# M4QIDB-SCH-01_Sheet2.net
KiCad netlist of a schematic drawn in Altium Designer
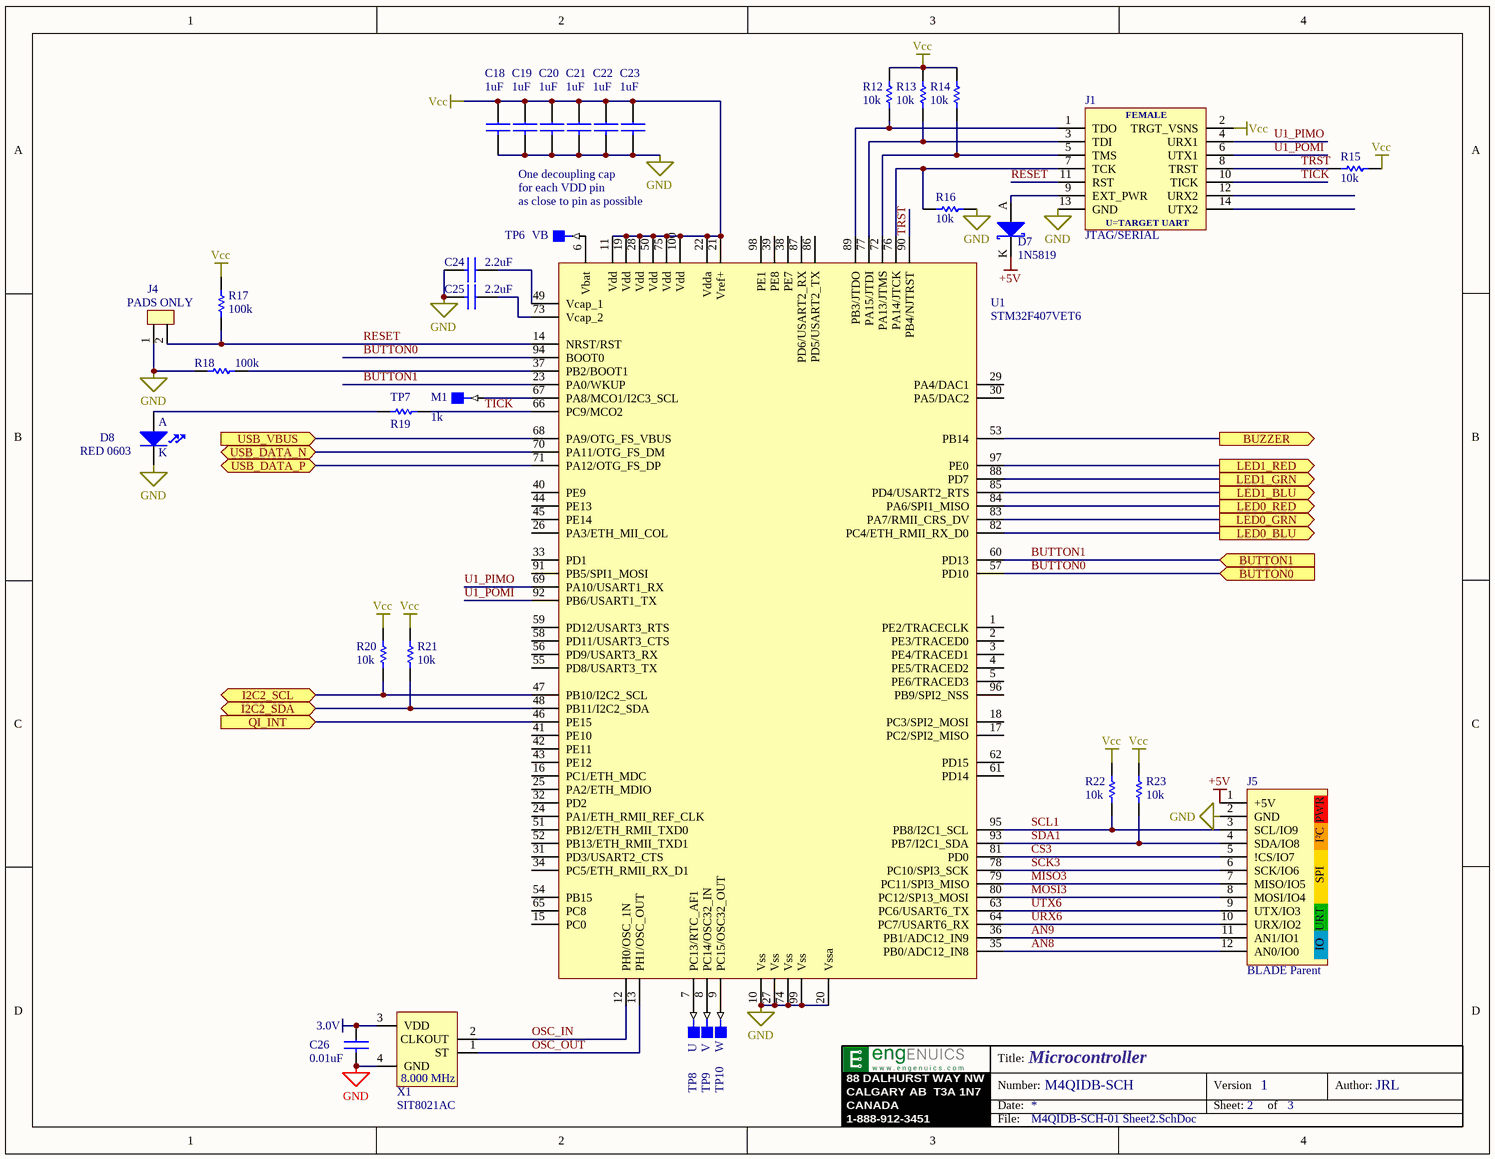
[diagram p0: M4QIDB-SCH-01 Sheet2.SchDoc]

(export (version "E")
  (design (tool "Eeschema 10.0.6"))
  (components
    (comp (ref "C18")
      (value "1uF")
      (footprint "0603 CAP3D")
      (fields
        (field (name "4. DIGI-KEY PART NUMBER") "587-1251-2-ND")
        (field (name "3. MANUFACTURER PART NUMBER") "EMK107BJ105KA-T")
        (field (name "5. INTERNAL PART NUMBER") "100009")
        (field (name "7. MODIFIED BY") "JRL")
      )
      (libsource (lib "PK Master Schematic Library") (part "CAPACITOR NON-POLARIZED"))
    )
    (comp (ref "C19")
      (value "1uF")
      (footprint "0603 CAP3D")
      (fields
        (field (name "4. DIGI-KEY PART NUMBER") "587-1251-2-ND")
        (field (name "3. MANUFACTURER PART NUMBER") "EMK107BJ105KA-T")
        (field (name "5. INTERNAL PART NUMBER") "100009")
        (field (name "7. MODIFIED BY") "JRL")
      )
      (libsource (lib "PK Master Schematic Library") (part "CAPACITOR NON-POLARIZED"))
    )
    (comp (ref "C20")
      (value "1uF")
      (footprint "0603 CAP3D")
      (fields
        (field (name "4. DIGI-KEY PART NUMBER") "587-1251-2-ND")
        (field (name "3. MANUFACTURER PART NUMBER") "EMK107BJ105KA-T")
        (field (name "5. INTERNAL PART NUMBER") "100009")
        (field (name "7. MODIFIED BY") "JRL")
      )
      (libsource (lib "PK Master Schematic Library") (part "CAPACITOR NON-POLARIZED"))
    )
    (comp (ref "C21")
      (value "1uF")
      (footprint "0603 CAP3D")
      (fields
        (field (name "4. DIGI-KEY PART NUMBER") "587-1251-2-ND")
        (field (name "3. MANUFACTURER PART NUMBER") "EMK107BJ105KA-T")
        (field (name "5. INTERNAL PART NUMBER") "100009")
        (field (name "7. MODIFIED BY") "JRL")
      )
      (libsource (lib "PK Master Schematic Library") (part "CAPACITOR NON-POLARIZED"))
    )
    (comp (ref "C22")
      (value "1uF")
      (footprint "0603 CAP3D")
      (fields
        (field (name "4. DIGI-KEY PART NUMBER") "587-1251-2-ND")
        (field (name "3. MANUFACTURER PART NUMBER") "EMK107BJ105KA-T")
        (field (name "5. INTERNAL PART NUMBER") "100009")
        (field (name "7. MODIFIED BY") "JRL")
      )
      (libsource (lib "PK Master Schematic Library") (part "CAPACITOR NON-POLARIZED"))
    )
    (comp (ref "C23")
      (value "1uF")
      (footprint "0603 CAP3D")
      (fields
        (field (name "4. DIGI-KEY PART NUMBER") "587-1251-2-ND")
        (field (name "3. MANUFACTURER PART NUMBER") "EMK107BJ105KA-T")
        (field (name "5. INTERNAL PART NUMBER") "100009")
        (field (name "7. MODIFIED BY") "JRL")
      )
      (libsource (lib "PK Master Schematic Library") (part "CAPACITOR NON-POLARIZED"))
    )
    (comp (ref "C24")
      (value "2.2uF")
      (footprint "0603 CAP3D")
      (fields
        (field (name "4. DIGI-KEY PART NUMBER") "C1608X5R1C225K/0.80")
        (field (name "3. MANUFACTURER PART NUMBER") "445-5157-1-ND")
        (field (name "7. MODIFIED BY") "JRL")
      )
      (libsource (lib "PK Master Schematic Library") (part "CAPACITOR NON-POLARIZED"))
    )
    (comp (ref "C25")
      (value "2.2uF")
      (footprint "0603 CAP3D")
      (fields
        (field (name "4. DIGI-KEY PART NUMBER") "C1608X5R1C225K/0.80")
        (field (name "3. MANUFACTURER PART NUMBER") "445-5157-1-ND")
        (field (name "7. MODIFIED BY") "JRL")
      )
      (libsource (lib "PK Master Schematic Library") (part "CAPACITOR NON-POLARIZED"))
    )
    (comp (ref "C26")
      (value "0.01uF")
      (footprint "0603 CAP3D")
      (fields
        (field (name "4. DIGI-KEY PART NUMBER") "1276-1051-2-ND")
        (field (name "3. MANUFACTURER PART NUMBER") "CL05B103KO5NNNC")
        (field (name "7. MODIFIED BY") "JRL")
      )
      (libsource (lib "Engenuics Master Schematic Library") (part "CAPACITOR NON-POLARIZED"))
    )
    (comp (ref "D7")
      (value "1N5819")
      (footprint "SOD123 AK")
      (fields
        (field (name "3. MANUFACTURER PART NUMBER") "1N5819HW-7-F")
        (field (name "4. DIGI-KEY PART NUMBER") "1N5819HW-FDITR-ND")
        (field (name "5. INTERNAL PART NUMBER") "100039")
        (field (name "7. MODIFIED BY") "JRL")
      )
      (libsource (lib "Engenuics Master Schematic Library") (part "DIODE SCHOTTKY AK"))
    )
    (comp (ref "D8")
      (value "RED 0603")
      (footprint "0603 AK")
      (fields
        (field (name "3. MANUFACTURER PART NUMBER") "APT1608SRCPRV")
        (field (name "4. DIGI-KEY PART NUMBER") "754-1122-2-ND")
        (field (name "7. MODIFIED BY") "JRL")
      )
      (libsource (lib "PK Master Schematic Library") (part "LED AK"))
    )
    (comp (ref "J1")
      (value "JTAG/SERIAL")
      (footprint "CONN 14POS 7X2 SMT FEMALE")
      (fields
        (field (name "3. MANUFACTURER PART NUMBER") "FLE-107-01-G-DV")
        (field (name "4. DIGI-KEY PART NUMBER") "SAM1226-07-ND")
        (field (name "7. MODIFIED BY") "JRL")
      )
      (libsource (lib "Engenuics Master Schematic Library") (part "CONN JTAG/SERIAL DEBUG 14POS FEMALE ENGENUICS"))
    )
    (comp (ref "J4")
      (value "PADS ONLY")
      (footprint "HDR1X2")
      (libsource (lib "PK Master Schematic Library") (part "CONN SIP 2"))
    )
    (comp (ref "J5")
      (value "BLADE Parent")
      (footprint "HDR1X12 ENGENUICS PARENT")
      (fields
        (field (name "3. MANUFACTURER PART NUMBER") "PPTC121LGBN-RC")
        (field (name "4. DIGI-KEY PART NUMBER") "S5448-ND")
        (field (name "5. INTERNAL PART NUMBER") "100031")
        (field (name "7. MODIFIED BY") "JRL")
      )
      (libsource (lib "Engenuics Master Schematic Library") (part "CONN ENGENUICS BLADE PARENT"))
    )
    (comp (ref "R12")
      (value "10k")
      (footprint "0603")
      (fields
        (field (name "4. DIGI-KEY PART NUMBER") "541-10.0KHTR-ND")
        (field (name "3. MANUFACTURER PART NUMBER") "CRCW060310K0FKEA")
        (field (name "5. INTERNAL PART NUMBER") "100079")
        (field (name "7. MODIFIED BY") "JRL")
      )
      (libsource (lib "altium-import") (part "root_1_RESISTOR_"))
    )
    (comp (ref "R13")
      (value "10k")
      (footprint "0603")
      (fields
        (field (name "4. DIGI-KEY PART NUMBER") "541-10.0KHTR-ND")
        (field (name "3. MANUFACTURER PART NUMBER") "CRCW060310K0FKEA")
        (field (name "5. INTERNAL PART NUMBER") "100079")
        (field (name "7. MODIFIED BY") "JRL")
      )
      (libsource (lib "altium-import") (part "root_1_RESISTOR_"))
    )
    (comp (ref "R14")
      (value "10k")
      (footprint "0603")
      (fields
        (field (name "4. DIGI-KEY PART NUMBER") "541-10.0KHTR-ND")
        (field (name "3. MANUFACTURER PART NUMBER") "CRCW060310K0FKEA")
        (field (name "5. INTERNAL PART NUMBER") "100079")
        (field (name "7. MODIFIED BY") "JRL")
      )
      (libsource (lib "altium-import") (part "root_1_RESISTOR_"))
    )
    (comp (ref "R15")
      (value "10k")
      (footprint "0603")
      (fields
        (field (name "4. DIGI-KEY PART NUMBER") "541-10.0KHTR-ND")
        (field (name "3. MANUFACTURER PART NUMBER") "CRCW060310K0FKEA")
        (field (name "5. INTERNAL PART NUMBER") "100079")
        (field (name "7. MODIFIED BY") "JRL")
      )
      (libsource (lib "altium-import") (part "root_2_RESISTOR_"))
    )
    (comp (ref "R16")
      (value "10k")
      (footprint "0603")
      (fields
        (field (name "4. DIGI-KEY PART NUMBER") "541-10.0KHTR-ND")
        (field (name "3. MANUFACTURER PART NUMBER") "CRCW060310K0FKEA")
        (field (name "5. INTERNAL PART NUMBER") "100079")
        (field (name "7. MODIFIED BY") "JRL")
      )
      (libsource (lib "altium-import") (part "root_2_RESISTOR_"))
    )
    (comp (ref "R17")
      (value "100k")
      (footprint "0603")
      (fields
        (field (name "4. DIGI-KEY PART NUMBER") "311-100KHRTR-ND")
        (field (name "3. MANUFACTURER PART NUMBER") "RC0603FR-07100KL")
        (field (name "5. INTERNAL PART NUMBER") "100078")
        (field (name "7. MODIFIED BY") "JRL")
      )
      (libsource (lib "altium-import") (part "root_1_RESISTOR_"))
    )
    (comp (ref "R18")
      (value "100k")
      (footprint "0603")
      (fields
        (field (name "4. DIGI-KEY PART NUMBER") "311-100KHRTR-ND")
        (field (name "3. MANUFACTURER PART NUMBER") "RC0603FR-07100KL")
        (field (name "5. INTERNAL PART NUMBER") "100078")
        (field (name "7. MODIFIED BY") "JRL")
      )
      (libsource (lib "altium-import") (part "root_2_RESISTOR_"))
    )
    (comp (ref "R19")
      (value "1k")
      (footprint "0603")
      (fields
        (field (name "4. DIGI-KEY PART NUMBER") "541-1.00KHCT-ND")
        (field (name "3. MANUFACTURER PART NUMBER") "CRCW06031K00FKEA")
        (field (name "7. MODIFIED BY") "KP")
      )
      (libsource (lib "PK Master Schematic Library") (part "RESISTOR"))
    )
    (comp (ref "R20")
      (value "10k")
      (footprint "0603")
      (fields
        (field (name "4. DIGI-KEY PART NUMBER") "541-10.0KHTR-ND")
        (field (name "3. MANUFACTURER PART NUMBER") "CRCW060310K0FKEA")
        (field (name "5. INTERNAL PART NUMBER") "100079")
        (field (name "7. MODIFIED BY") "JRL")
      )
      (libsource (lib "altium-import") (part "root_1_RESISTOR_"))
    )
    (comp (ref "R21")
      (value "10k")
      (footprint "0603")
      (fields
        (field (name "4. DIGI-KEY PART NUMBER") "541-10.0KHTR-ND")
        (field (name "3. MANUFACTURER PART NUMBER") "CRCW060310K0FKEA")
        (field (name "5. INTERNAL PART NUMBER") "100079")
        (field (name "7. MODIFIED BY") "JRL")
      )
      (libsource (lib "altium-import") (part "root_1_RESISTOR_"))
    )
    (comp (ref "R22")
      (value "10k")
      (footprint "0603")
      (fields
        (field (name "4. DIGI-KEY PART NUMBER") "541-10.0KHTR-ND")
        (field (name "3. MANUFACTURER PART NUMBER") "CRCW060310K0FKEA")
        (field (name "5. INTERNAL PART NUMBER") "100079")
        (field (name "7. MODIFIED BY") "JRL")
      )
      (libsource (lib "altium-import") (part "root_1_RESISTOR_"))
    )
    (comp (ref "R23")
      (value "10k")
      (footprint "0603")
      (fields
        (field (name "4. DIGI-KEY PART NUMBER") "541-10.0KHTR-ND")
        (field (name "3. MANUFACTURER PART NUMBER") "CRCW060310K0FKEA")
        (field (name "5. INTERNAL PART NUMBER") "100079")
        (field (name "7. MODIFIED BY") "JRL")
      )
      (libsource (lib "altium-import") (part "root_1_RESISTOR_"))
    )
    (comp (ref "TP6")
      (value "VB")
      (footprint "TEST POINT SMT")
      (fields (field (name "7. MODIFIED BY") "JRL"))
      (libsource (lib "PK Master Schematic Library") (part "TEST POINT SMT"))
    )
    (comp (ref "TP7")
      (value "M1")
      (footprint "TEST POINT SMT")
      (fields (field (name "7. MODIFIED BY") "JRL"))
      (libsource (lib "PK Master Schematic Library") (part "TEST POINT SMT"))
    )
    (comp (ref "TP8")
      (value "U")
      (footprint "TEST POINT SMT")
      (fields (field (name "7. MODIFIED BY") "JRL"))
      (libsource (lib "PK Master Schematic Library") (part "TEST POINT SMT"))
    )
    (comp (ref "TP9")
      (value "V")
      (footprint "TEST POINT SMT")
      (fields (field (name "7. MODIFIED BY") "JRL"))
      (libsource (lib "PK Master Schematic Library") (part "TEST POINT SMT"))
    )
    (comp (ref "TP10")
      (value "W")
      (footprint "TEST POINT SMT")
      (fields (field (name "7. MODIFIED BY") "JRL"))
      (libsource (lib "PK Master Schematic Library") (part "TEST POINT SMT"))
    )
    (comp (ref "U1")
      (value "STM32F407VET6")
      (footprint "LQFP100")
      (fields (field (name "4. DIGI-KEY PART NUMBER") "497-12075-ND") (field (name "7. MODIFIED BY") "JRL"))
      (libsource (lib "M4QIDB-PRJ-01_1") (part "MCU STM32F407Vx M4QIDB"))
    )
    (comp (ref "X1")
      (value "SIT8021AC")
      (footprint "CSP 1.55mm x 0.85mm")
      (fields
        (field (name "3. MANUFACTURER PART NUMBER") "SiT8021AC-J4-XXS-8.000000D")
        (field (name "7. MODIFIED BY") "JRL")
      )
      (libsource (lib "Engenuics Master Schematic Library") (part "IC OSCILLATOR SIT8021AC"))
    )
  )
  (nets
    (net (code "1") (name "+5V") (class "Default")
      (node (ref "D7") (pin "K") (pinfunction "K_K") (pintype "passive"))
      (node (ref "J5") (pin "1") (pinfunction "+5V_1") (pintype "passive"))
    )
    (net (code "2") (name "/AN8") (class "Default")
      (node (ref "J5") (pin "12") (pinfunction "AN0/IO0_12") (pintype "passive"))
      (node (ref "U1") (pin "35") (pinfunction "PB0/ADC12_IN8_35") (pintype "passive"))
    )
    (net (code "3") (name "/AN9") (class "Default")
      (node (ref "J5") (pin "11") (pinfunction "AN1/IO1_11") (pintype "passive"))
      (node (ref "U1") (pin "36") (pinfunction "PB1/ADC12_IN9_36") (pintype "passive"))
    )
    (net (code "4") (name "/BUTTON0") (class "Default")
      (node (ref "U1") (pin "57") (pinfunction "PD10_57") (pintype "passive"))
      (node (ref "U1") (pin "94") (pinfunction "BOOT0_94") (pintype "passive"))
    )
    (net (code "5") (name "/BUTTON1") (class "Default")
      (node (ref "U1") (pin "23") (pinfunction "PA0/WKUP_23") (pintype "passive"))
      (node (ref "U1") (pin "60") (pinfunction "PD13_60") (pintype "passive"))
    )
    (net (code "6") (name "/BUZZER") (class "Default")
      (node (ref "U1") (pin "53") (pinfunction "PB14_53") (pintype "passive"))
    )
    (net (code "7") (name "/CS3") (class "Default")
      (node (ref "J5") (pin "5") (pinfunction "!CS/IO7_5") (pintype "passive"))
      (node (ref "U1") (pin "81") (pinfunction "PD0_81") (pintype "passive"))
    )
    (net (code "8") (name "/I2C2_SCL") (class "Default")
      (node (ref "R20") (pin "1") (pinfunction "1_1") (pintype "passive"))
      (node (ref "U1") (pin "47") (pinfunction "PB10/I2C2_SCL_47") (pintype "passive"))
    )
    (net (code "9") (name "/I2C2_SDA") (class "Default")
      (node (ref "R21") (pin "1") (pinfunction "1_1") (pintype "passive"))
      (node (ref "U1") (pin "48") (pinfunction "PB11/I2C2_SDA_48") (pintype "passive"))
    )
    (net (code "10") (name "/LED0_BLU") (class "Default")
      (node (ref "U1") (pin "82") (pinfunction "PC4/ETH_RMII_RX_D0_82") (pintype "passive"))
    )
    (net (code "11") (name "/LED0_GRN") (class "Default")
      (node (ref "U1") (pin "83") (pinfunction "PA7/RMII_CRS_DV_83") (pintype "passive"))
    )
    (net (code "12") (name "/LED0_RED") (class "Default")
      (node (ref "U1") (pin "84") (pinfunction "PA6/SPI1_MISO_84") (pintype "passive"))
    )
    (net (code "13") (name "/LED1_BLU") (class "Default")
      (node (ref "U1") (pin "85") (pinfunction "PD4/USART2_RTS_85") (pintype "passive"))
    )
    (net (code "14") (name "/LED1_GRN") (class "Default")
      (node (ref "U1") (pin "88") (pinfunction "PD7_88") (pintype "passive"))
    )
    (net (code "15") (name "/LED1_RED") (class "Default")
      (node (ref "U1") (pin "97") (pinfunction "PE0_97") (pintype "passive"))
    )
    (net (code "16") (name "/MISO3") (class "Default")
      (node (ref "J5") (pin "7") (pinfunction "MISO/IO5_7") (pintype "passive"))
      (node (ref "U1") (pin "79") (pinfunction "PC11/SPI3_MISO_79") (pintype "passive"))
    )
    (net (code "17") (name "/MOSI3") (class "Default")
      (node (ref "J5") (pin "8") (pinfunction "MOSI/IO4_8") (pintype "passive"))
      (node (ref "U1") (pin "80") (pinfunction "PC12/SP13_MOSI_80") (pintype "passive"))
    )
    (net (code "18") (name "/OSC_IN") (class "Default")
      (node (ref "U1") (pin "12") (pinfunction "PH0/OSC_1N_12") (pintype "passive"))
      (node (ref "X1") (pin "2") (pinfunction "CLKOUT_2") (pintype "passive"))
    )
    (net (code "19") (name "/OSC_OUT") (class "Default")
      (node (ref "U1") (pin "13") (pinfunction "PH1/OSC_OUT_13") (pintype "passive"))
      (node (ref "X1") (pin "1") (pinfunction "ST_1") (pintype "passive"))
    )
    (net (code "20") (name "/QI_INT") (class "Default")
      (node (ref "U1") (pin "46") (pinfunction "PE15_46") (pintype "passive"))
    )
    (net (code "21") (name "/RESET") (class "Default")
      (node (ref "J1") (pin "11") (pinfunction "RST_11") (pintype "passive"))
      (node (ref "J4") (pin "2") (pintype "passive"))
      (node (ref "R17") (pin "1") (pinfunction "1_1") (pintype "passive"))
      (node (ref "U1") (pin "14") (pinfunction "NRST/RST_14") (pintype "passive"))
    )
    (net (code "22") (name "/SCK3") (class "Default")
      (node (ref "J5") (pin "6") (pinfunction "SCK/IO6_6") (pintype "passive"))
      (node (ref "U1") (pin "78") (pinfunction "PC10/SPI3_SCK_78") (pintype "passive"))
    )
    (net (code "23") (name "/SCL1") (class "Default")
      (node (ref "J5") (pin "3") (pinfunction "SCL/IO9_3") (pintype "passive"))
      (node (ref "R22") (pin "1") (pinfunction "1_1") (pintype "passive"))
      (node (ref "U1") (pin "95") (pinfunction "PB8/I2C1_SCL_95") (pintype "passive"))
    )
    (net (code "24") (name "/SDA1") (class "Default")
      (node (ref "J5") (pin "4") (pinfunction "SDA/IO8_4") (pintype "passive"))
      (node (ref "R23") (pin "1") (pinfunction "1_1") (pintype "passive"))
      (node (ref "U1") (pin "93") (pinfunction "PB7/I2C1_SDA_93") (pintype "passive"))
    )
    (net (code "25") (name "/TICK") (class "Default")
      (node (ref "J1") (pin "10") (pinfunction "TICK_10") (pintype "passive"))
      (node (ref "R19") (pin "2") (pinfunction "2_2") (pintype "passive"))
      (node (ref "U1") (pin "66") (pinfunction "PC9/MCO2_66") (pintype "passive"))
    )
    (net (code "26") (name "/TRST") (class "Default")
      (node (ref "J1") (pin "8") (pinfunction "TRST_8") (pintype "passive"))
      (node (ref "R15") (pin "2") (pinfunction "2_2") (pintype "passive"))
      (node (ref "U1") (pin "90") (pinfunction "PB4/NJTRST_90") (pintype "passive"))
    )
    (net (code "27") (name "/U1_PIMO") (class "Default")
      (node (ref "J1") (pin "4") (pinfunction "URX1_4") (pintype "passive"))
      (node (ref "U1") (pin "69") (pinfunction "PA10/USART1_RX_69") (pintype "passive"))
    )
    (net (code "28") (name "/U1_POMI") (class "Default")
      (node (ref "J1") (pin "6") (pinfunction "UTX1_6") (pintype "passive"))
      (node (ref "U1") (pin "92") (pinfunction "PB6/USART1_TX_92") (pintype "passive"))
    )
    (net (code "29") (name "/URX6") (class "Default")
      (node (ref "J5") (pin "10") (pinfunction "URX/IO2_10") (pintype "passive"))
      (node (ref "U1") (pin "64") (pinfunction "PC7/USART6_RX_64") (pintype "passive"))
    )
    (net (code "30") (name "/USB_DATA_N") (class "Default")
      (node (ref "U1") (pin "70") (pinfunction "PA11/OTG_FS_DM_70") (pintype "passive"))
    )
    (net (code "31") (name "/USB_DATA_P") (class "Default")
      (node (ref "U1") (pin "71") (pinfunction "PA12/OTG_FS_DP_71") (pintype "passive"))
    )
    (net (code "32") (name "/USB_VBUS") (class "Default")
      (node (ref "U1") (pin "68") (pinfunction "PA9/OTG_FS_VBUS_68") (pintype "passive"))
    )
    (net (code "33") (name "/UTX6") (class "Default")
      (node (ref "J5") (pin "9") (pinfunction "UTX/IO3_9") (pintype "passive"))
      (node (ref "U1") (pin "63") (pinfunction "PC6/USART6_TX_63") (pintype "passive"))
    )
    (net (code "34") (name "3.0V") (class "Default")
      (node (ref "C26") (pin "1") (pinfunction "1_1") (pintype "passive"))
      (node (ref "X1") (pin "3") (pinfunction "VDD_3") (pintype "passive"))
    )
    (net (code "35") (name "GND") (class "Default")
      (node (ref "C18") (pin "2") (pinfunction "2_2") (pintype "passive"))
      (node (ref "C19") (pin "2") (pinfunction "2_2") (pintype "passive"))
      (node (ref "C20") (pin "2") (pinfunction "2_2") (pintype "passive"))
      (node (ref "C21") (pin "2") (pinfunction "2_2") (pintype "passive"))
      (node (ref "C22") (pin "2") (pinfunction "2_2") (pintype "passive"))
      (node (ref "C23") (pin "2") (pinfunction "2_2") (pintype "passive"))
      (node (ref "C24") (pin "2") (pinfunction "2_2") (pintype "passive"))
      (node (ref "C25") (pin "2") (pinfunction "2_2") (pintype "passive"))
      (node (ref "C26") (pin "2") (pinfunction "2_2") (pintype "passive"))
      (node (ref "D8") (pin "K") (pinfunction "K_K") (pintype "passive"))
      (node (ref "J1") (pin "13") (pinfunction "GND_13") (pintype "power_in"))
      (node (ref "J4") (pin "1") (pintype "passive"))
      (node (ref "J5") (pin "2") (pinfunction "GND_2") (pintype "passive"))
      (node (ref "R16") (pin "1") (pinfunction "1_1") (pintype "passive"))
      (node (ref "R18") (pin "2") (pinfunction "2_2") (pintype "passive"))
      (node (ref "U1") (pin "10") (pinfunction "Vss_10") (pintype "passive"))
      (node (ref "U1") (pin "20") (pinfunction "Vssa_20") (pintype "passive"))
      (node (ref "U1") (pin "27") (pinfunction "Vss_27") (pintype "passive"))
      (node (ref "U1") (pin "74") (pinfunction "Vss_74") (pintype "passive"))
      (node (ref "U1") (pin "99") (pinfunction "Vss_99") (pintype "passive"))
      (node (ref "X1") (pin "4") (pinfunction "GND_4") (pintype "passive"))
    )
    (net (code "36") (name "Net-(D8-PadA)") (class "Default")
      (node (ref "D8") (pin "A") (pinfunction "A_A") (pintype "passive"))
      (node (ref "R19") (pin "1") (pinfunction "1_1") (pintype "passive"))
    )
    (net (code "37") (name "Net-(J1-EXT_PWR)") (class "Default")
      (node (ref "D7") (pin "A") (pinfunction "A_A") (pintype "passive"))
      (node (ref "J1") (pin "9") (pinfunction "EXT_PWR_9") (pintype "passive"))
    )
    (net (code "38") (name "Net-(J1-TCK)") (class "Default")
      (node (ref "J1") (pin "7") (pinfunction "TCK_7") (pintype "passive"))
      (node (ref "R16") (pin "2") (pinfunction "2_2") (pintype "passive"))
      (node (ref "U1") (pin "76") (pinfunction "PA14/JTCK_76") (pintype "passive"))
    )
    (net (code "39") (name "Net-(J1-TDI)") (class "Default")
      (node (ref "J1") (pin "3") (pinfunction "TDI_3") (pintype "passive"))
      (node (ref "R13") (pin "1") (pinfunction "1_1") (pintype "passive"))
      (node (ref "U1") (pin "77") (pinfunction "PA15/JTDI_77") (pintype "passive"))
    )
    (net (code "40") (name "Net-(J1-TDO)") (class "Default")
      (node (ref "J1") (pin "1") (pinfunction "TDO_1") (pintype "passive"))
      (node (ref "R12") (pin "1") (pinfunction "1_1") (pintype "passive"))
      (node (ref "U1") (pin "89") (pinfunction "PB3/JTDO_89") (pintype "passive"))
    )
    (net (code "41") (name "Net-(J1-TMS)") (class "Default")
      (node (ref "J1") (pin "5") (pinfunction "TMS_5") (pintype "passive"))
      (node (ref "R14") (pin "1") (pinfunction "1_1") (pintype "passive"))
      (node (ref "U1") (pin "72") (pinfunction "PA13/JTMS_72") (pintype "passive"))
    )
    (net (code "42") (name "Net-(U1-PA8{slash}MCO1{slash}I2C3_SCL)") (class "Default")
      (node (ref "TP7") (pin "1") (pinfunction "1_1") (pintype "input"))
      (node (ref "U1") (pin "67") (pinfunction "PA8/MCO1/I2C3_SCL_67") (pintype "passive"))
    )
    (net (code "43") (name "Net-(U1-PB2{slash}BOOT1)") (class "Default")
      (node (ref "R18") (pin "1") (pinfunction "1_1") (pintype "passive"))
      (node (ref "U1") (pin "37") (pinfunction "PB2/BOOT1_37") (pintype "passive"))
    )
    (net (code "44") (name "Net-(U1-PC13{slash}RTC_AF1)") (class "Default")
      (node (ref "TP8") (pin "1") (pinfunction "1_1") (pintype "input"))
      (node (ref "U1") (pin "7") (pinfunction "PC13/RTC_AF1_7") (pintype "passive"))
    )
    (net (code "45") (name "Net-(U1-PC14{slash}OSC32_IN)") (class "Default")
      (node (ref "TP9") (pin "1") (pinfunction "1_1") (pintype "input"))
      (node (ref "U1") (pin "8") (pinfunction "PC14/OSC32_IN_8") (pintype "passive"))
    )
    (net (code "46") (name "Net-(U1-PC15{slash}OSC32_OUT)") (class "Default")
      (node (ref "TP10") (pin "1") (pinfunction "1_1") (pintype "input"))
      (node (ref "U1") (pin "9") (pinfunction "PC15/OSC32_OUT_9") (pintype "passive"))
    )
    (net (code "47") (name "Net-(U1-Vbat)") (class "Default")
      (node (ref "TP6") (pin "1") (pinfunction "1_1") (pintype "input"))
      (node (ref "U1") (pin "6") (pinfunction "Vbat_6") (pintype "passive"))
    )
    (net (code "48") (name "Net-(U1-Vcap_1)") (class "Default")
      (node (ref "C24") (pin "1") (pinfunction "1_1") (pintype "passive"))
      (node (ref "U1") (pin "49") (pinfunction "Vcap_1_49") (pintype "passive"))
    )
    (net (code "49") (name "Net-(U1-Vcap_2)") (class "Default")
      (node (ref "C25") (pin "1") (pinfunction "1_1") (pintype "passive"))
      (node (ref "U1") (pin "73") (pinfunction "Vcap_2_73") (pintype "passive"))
    )
    (net (code "50") (name "Vcc") (class "Default")
      (node (ref "C18") (pin "1") (pinfunction "1_1") (pintype "passive"))
      (node (ref "C19") (pin "1") (pinfunction "1_1") (pintype "passive"))
      (node (ref "C20") (pin "1") (pinfunction "1_1") (pintype "passive"))
      (node (ref "C21") (pin "1") (pinfunction "1_1") (pintype "passive"))
      (node (ref "C22") (pin "1") (pinfunction "1_1") (pintype "passive"))
      (node (ref "C23") (pin "1") (pinfunction "1_1") (pintype "passive"))
      (node (ref "J1") (pin "2") (pinfunction "TRGT_VSNS_2") (pintype "passive"))
      (node (ref "R12") (pin "2") (pinfunction "2_2") (pintype "passive"))
      (node (ref "R13") (pin "2") (pinfunction "2_2") (pintype "passive"))
      (node (ref "R14") (pin "2") (pinfunction "2_2") (pintype "passive"))
      (node (ref "R15") (pin "1") (pinfunction "1_1") (pintype "passive"))
      (node (ref "R17") (pin "2") (pinfunction "2_2") (pintype "passive"))
      (node (ref "R20") (pin "2") (pinfunction "2_2") (pintype "passive"))
      (node (ref "R21") (pin "2") (pinfunction "2_2") (pintype "passive"))
      (node (ref "R22") (pin "2") (pinfunction "2_2") (pintype "passive"))
      (node (ref "R23") (pin "2") (pinfunction "2_2") (pintype "passive"))
      (node (ref "U1") (pin "100") (pinfunction "Vdd_100") (pintype "passive"))
      (node (ref "U1") (pin "11") (pinfunction "Vdd_11") (pintype "passive"))
      (node (ref "U1") (pin "19") (pinfunction "Vdd_19") (pintype "passive"))
      (node (ref "U1") (pin "21") (pinfunction "Vref+_21") (pintype "passive"))
      (node (ref "U1") (pin "22") (pinfunction "Vdda_22") (pintype "passive"))
      (node (ref "U1") (pin "28") (pinfunction "Vdd_28") (pintype "passive"))
      (node (ref "U1") (pin "50") (pinfunction "Vdd_50") (pintype "passive"))
      (node (ref "U1") (pin "75") (pinfunction "Vdd_75") (pintype "passive"))
    )
    (net (code "51") (name "unconnected-(J1-URX2-Pad12)") (class "Default")
      (node (ref "J1") (pin "12") (pinfunction "URX2_12") (pintype "passive"))
    )
    (net (code "52") (name "unconnected-(J1-UTX2-Pad14)") (class "Default")
      (node (ref "J1") (pin "14") (pinfunction "UTX2_14") (pintype "passive"))
    )
    (net (code "53") (name "unconnected-(U1-PA1{slash}ETH_RMII_REF_CLK-Pad24)") (class "Default")
      (node (ref "U1") (pin "24") (pinfunction "PA1/ETH_RMII_REF_CLK_24") (pintype "passive"))
    )
    (net (code "54") (name "unconnected-(U1-PA2{slash}ETH_MDIO-Pad25)") (class "Default")
      (node (ref "U1") (pin "25") (pinfunction "PA2/ETH_MDIO_25") (pintype "passive"))
    )
    (net (code "55") (name "unconnected-(U1-PA3{slash}ETH_MII_COL-Pad26)") (class "Default")
      (node (ref "U1") (pin "26") (pinfunction "PA3/ETH_MII_COL_26") (pintype "passive"))
    )
    (net (code "56") (name "unconnected-(U1-PA4{slash}DAC1-Pad29)") (class "Default")
      (node (ref "U1") (pin "29") (pinfunction "PA4/DAC1_29") (pintype "passive"))
    )
    (net (code "57") (name "unconnected-(U1-PA5{slash}DAC2-Pad30)") (class "Default")
      (node (ref "U1") (pin "30") (pinfunction "PA5/DAC2_30") (pintype "passive"))
    )
    (net (code "58") (name "unconnected-(U1-PB5{slash}SPI1_MOSI-Pad91)") (class "Default")
      (node (ref "U1") (pin "91") (pinfunction "PB5/SPI1_MOSI_91") (pintype "passive"))
    )
    (net (code "59") (name "unconnected-(U1-PB9{slash}SPI2_NSS-Pad96)") (class "Default")
      (node (ref "U1") (pin "96") (pinfunction "PB9/SPI2_NSS_96") (pintype "passive"))
    )
    (net (code "60") (name "unconnected-(U1-PB12{slash}ETH_RMII_TXD0-Pad51)") (class "Default")
      (node (ref "U1") (pin "51") (pinfunction "PB12/ETH_RMII_TXD0_51") (pintype "passive"))
    )
    (net (code "61") (name "unconnected-(U1-PB13{slash}ETH_RMII_TXD1-Pad52)") (class "Default")
      (node (ref "U1") (pin "52") (pinfunction "PB13/ETH_RMII_TXD1_52") (pintype "passive"))
    )
    (net (code "62") (name "unconnected-(U1-PB15-Pad54)") (class "Default")
      (node (ref "U1") (pin "54") (pinfunction "PB15_54") (pintype "passive"))
    )
    (net (code "63") (name "unconnected-(U1-PC0-Pad15)") (class "Default")
      (node (ref "U1") (pin "15") (pinfunction "PC0_15") (pintype "passive"))
    )
    (net (code "64") (name "unconnected-(U1-PC1{slash}ETH_MDC-Pad16)") (class "Default")
      (node (ref "U1") (pin "16") (pinfunction "PC1/ETH_MDC_16") (pintype "passive"))
    )
    (net (code "65") (name "unconnected-(U1-PC2{slash}SPI2_MISO-Pad17)") (class "Default")
      (node (ref "U1") (pin "17") (pinfunction "PC2/SPI2_MISO_17") (pintype "passive"))
    )
    (net (code "66") (name "unconnected-(U1-PC3{slash}SPI2_MOSI-Pad18)") (class "Default")
      (node (ref "U1") (pin "18") (pinfunction "PC3/SPI2_MOSI_18") (pintype "passive"))
    )
    (net (code "67") (name "unconnected-(U1-PC5{slash}ETH_RMII_RX_D1-Pad34)") (class "Default")
      (node (ref "U1") (pin "34") (pinfunction "PC5/ETH_RMII_RX_D1_34") (pintype "passive"))
    )
    (net (code "68") (name "unconnected-(U1-PC8-Pad65)") (class "Default")
      (node (ref "U1") (pin "65") (pinfunction "PC8_65") (pintype "passive"))
    )
    (net (code "69") (name "unconnected-(U1-PD1-Pad33)") (class "Default")
      (node (ref "U1") (pin "33") (pinfunction "PD1_33") (pintype "passive"))
    )
    (net (code "70") (name "unconnected-(U1-PD2-Pad32)") (class "Default")
      (node (ref "U1") (pin "32") (pinfunction "PD2_32") (pintype "passive"))
    )
    (net (code "71") (name "unconnected-(U1-PD3{slash}USART2_CTS-Pad31)") (class "Default")
      (node (ref "U1") (pin "31") (pinfunction "PD3/USART2_CTS_31") (pintype "passive"))
    )
    (net (code "72") (name "unconnected-(U1-PD5{slash}USART2_TX-Pad86)") (class "Default")
      (node (ref "U1") (pin "86") (pinfunction "PD5/USART2_TX_86") (pintype "passive"))
    )
    (net (code "73") (name "unconnected-(U1-PD6{slash}USART2_RX-Pad87)") (class "Default")
      (node (ref "U1") (pin "87") (pinfunction "PD6/USART2_RX_87") (pintype "passive"))
    )
    (net (code "74") (name "unconnected-(U1-PD8{slash}USART3_TX-Pad55)") (class "Default")
      (node (ref "U1") (pin "55") (pinfunction "PD8/USART3_TX_55") (pintype "passive"))
    )
    (net (code "75") (name "unconnected-(U1-PD9{slash}USART3_RX-Pad56)") (class "Default")
      (node (ref "U1") (pin "56") (pinfunction "PD9/USART3_RX_56") (pintype "passive"))
    )
    (net (code "76") (name "unconnected-(U1-PD11{slash}USART3_CTS-Pad58)") (class "Default")
      (node (ref "U1") (pin "58") (pinfunction "PD11/USART3_CTS_58") (pintype "passive"))
    )
    (net (code "77") (name "unconnected-(U1-PD12{slash}USART3_RTS-Pad59)") (class "Default")
      (node (ref "U1") (pin "59") (pinfunction "PD12/USART3_RTS_59") (pintype "passive"))
    )
    (net (code "78") (name "unconnected-(U1-PD14-Pad61)") (class "Default")
      (node (ref "U1") (pin "61") (pinfunction "PD14_61") (pintype "passive"))
    )
    (net (code "79") (name "unconnected-(U1-PD15-Pad62)") (class "Default")
      (node (ref "U1") (pin "62") (pinfunction "PD15_62") (pintype "passive"))
    )
    (net (code "80") (name "unconnected-(U1-PE1-Pad98)") (class "Default")
      (node (ref "U1") (pin "98") (pinfunction "PE1_98") (pintype "passive"))
    )
    (net (code "81") (name "unconnected-(U1-PE2{slash}TRACECLK-Pad1)") (class "Default")
      (node (ref "U1") (pin "1") (pinfunction "PE2/TRACECLK_1") (pintype "passive"))
    )
    (net (code "82") (name "unconnected-(U1-PE3{slash}TRACED0-Pad2)") (class "Default")
      (node (ref "U1") (pin "2") (pinfunction "PE3/TRACED0_2") (pintype "passive"))
    )
    (net (code "83") (name "unconnected-(U1-PE4{slash}TRACED1-Pad3)") (class "Default")
      (node (ref "U1") (pin "3") (pinfunction "PE4/TRACED1_3") (pintype "passive"))
    )
    (net (code "84") (name "unconnected-(U1-PE5{slash}TRACED2-Pad4)") (class "Default")
      (node (ref "U1") (pin "4") (pinfunction "PE5/TRACED2_4") (pintype "passive"))
    )
    (net (code "85") (name "unconnected-(U1-PE6{slash}TRACED3-Pad5)") (class "Default")
      (node (ref "U1") (pin "5") (pinfunction "PE6/TRACED3_5") (pintype "passive"))
    )
    (net (code "86") (name "unconnected-(U1-PE7-Pad38)") (class "Default")
      (node (ref "U1") (pin "38") (pinfunction "PE7_38") (pintype "passive"))
    )
    (net (code "87") (name "unconnected-(U1-PE8-Pad39)") (class "Default")
      (node (ref "U1") (pin "39") (pinfunction "PE8_39") (pintype "passive"))
    )
    (net (code "88") (name "unconnected-(U1-PE9-Pad40)") (class "Default")
      (node (ref "U1") (pin "40") (pinfunction "PE9_40") (pintype "passive"))
    )
    (net (code "89") (name "unconnected-(U1-PE10-Pad41)") (class "Default")
      (node (ref "U1") (pin "41") (pinfunction "PE10_41") (pintype "passive"))
    )
    (net (code "90") (name "unconnected-(U1-PE11-Pad42)") (class "Default")
      (node (ref "U1") (pin "42") (pinfunction "PE11_42") (pintype "passive"))
    )
    (net (code "91") (name "unconnected-(U1-PE12-Pad43)") (class "Default")
      (node (ref "U1") (pin "43") (pinfunction "PE12_43") (pintype "passive"))
    )
    (net (code "92") (name "unconnected-(U1-PE13-Pad44)") (class "Default")
      (node (ref "U1") (pin "44") (pinfunction "PE13_44") (pintype "passive"))
    )
    (net (code "93") (name "unconnected-(U1-PE14-Pad45)") (class "Default")
      (node (ref "U1") (pin "45") (pinfunction "PE14_45") (pintype "passive"))
    )
  )
)
